# lps_display_rev_g_p1.net
KiCad netlist of a schematic drawn in Altium Designer
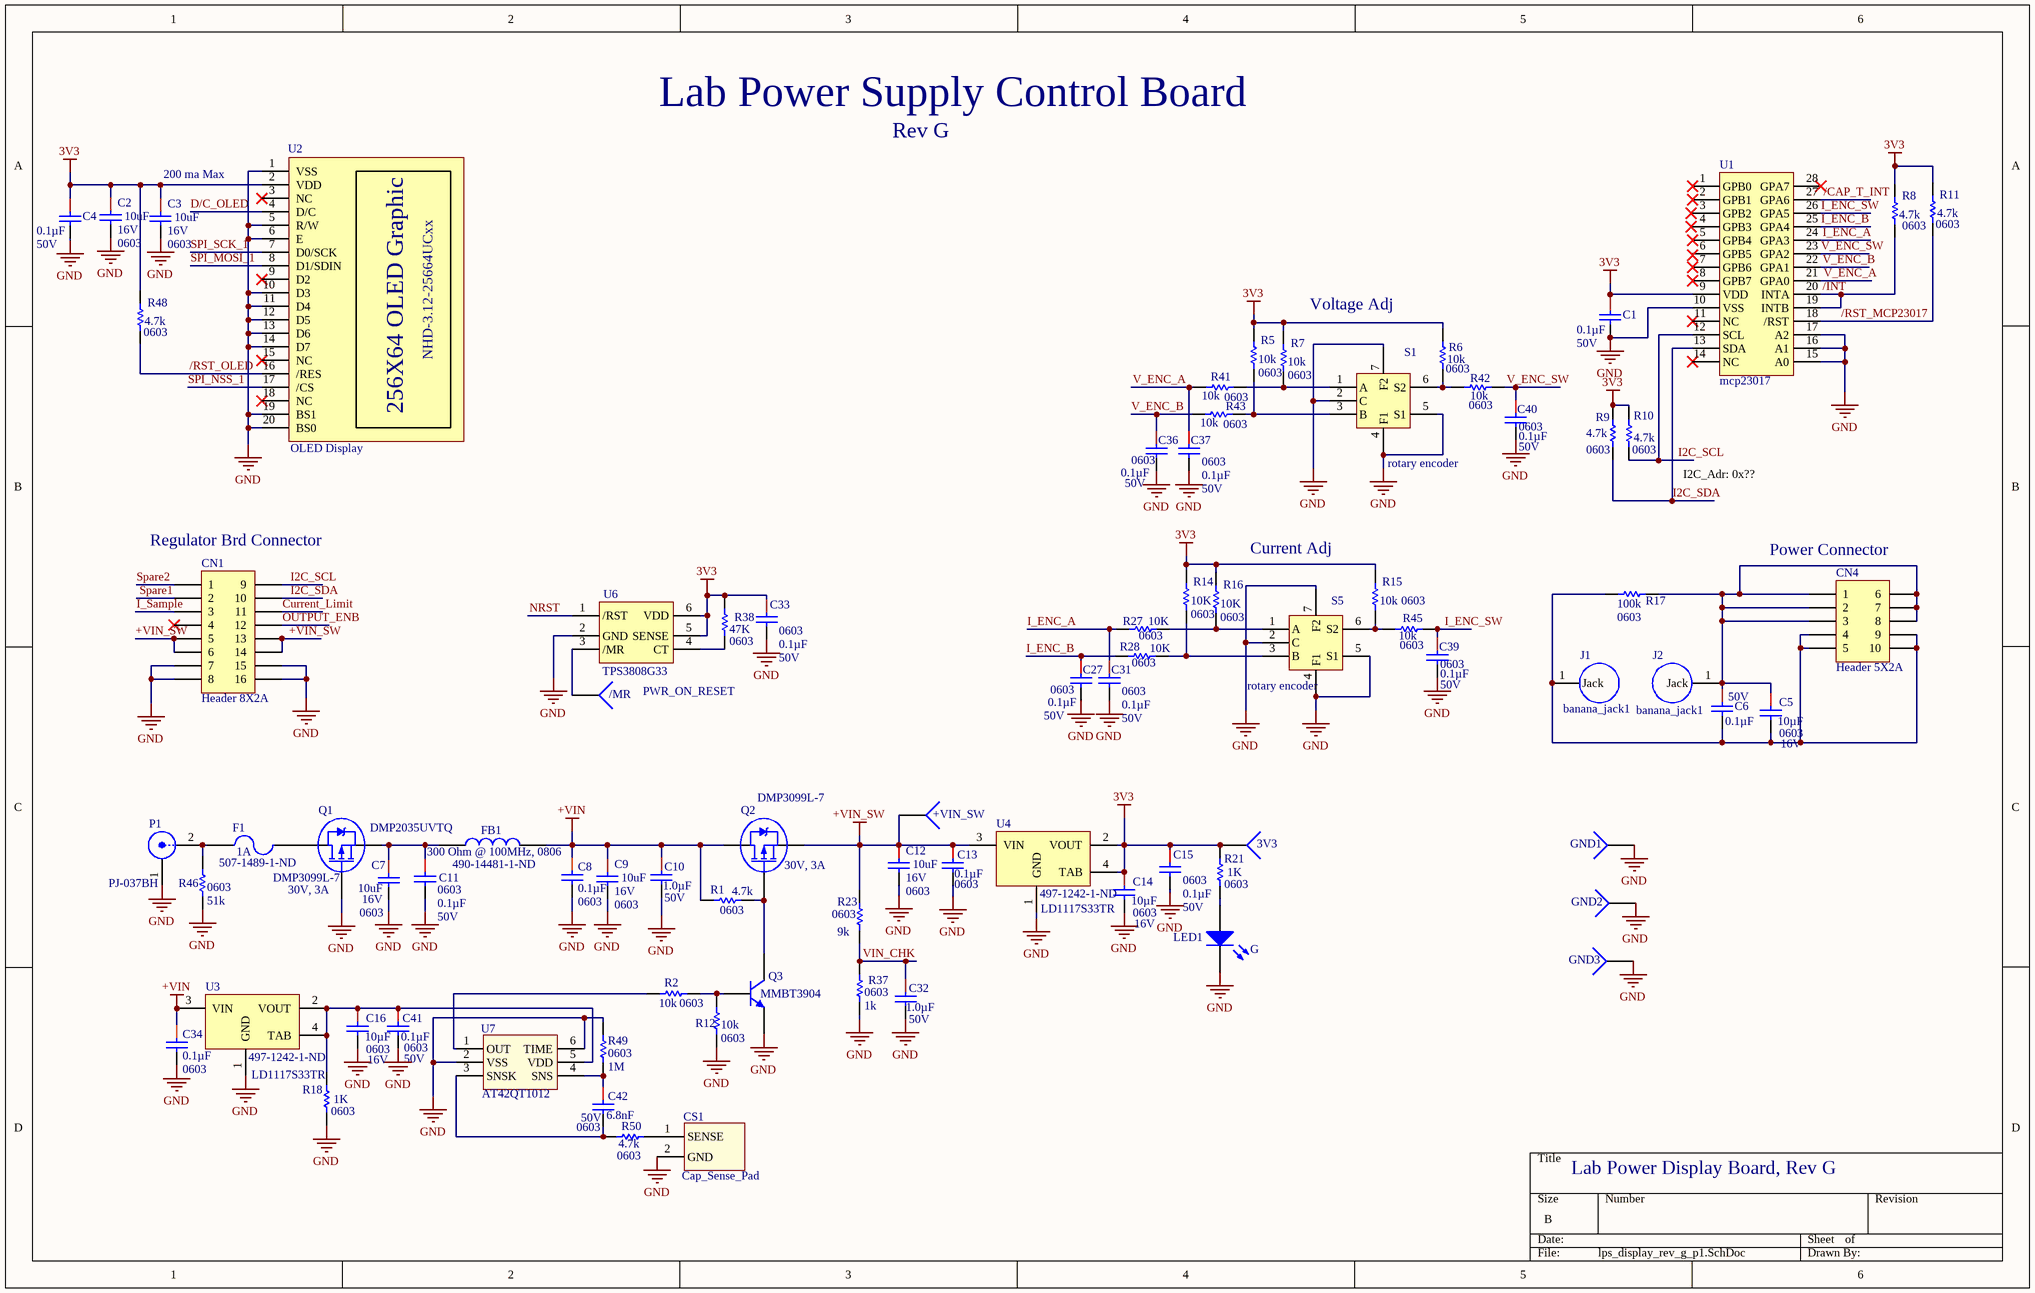
[diagram p0: lps_display_rev_g_p1.SchDoc]

(export (version "E")
  (design (tool "Eeschema 10.0.6"))
  (components
    (comp (ref "+VIN_SW")
      (value "~")
      (footprint "TestPoint-TH 35 mil")
      (description "Test Point")
      (libsource (lib "OLogic-Misc") (part "TestPoint"))
    )
    (comp (ref "/MR")
      (value "~")
      (footprint "TestPoint-TH 35 mil")
      (description "Test Point")
      (libsource (lib "OLogic-Misc") (part "TestPoint"))
    )
    (comp (ref "3V3")
      (value "~")
      (footprint "TestPoint-TH 35 mil")
      (description "Test Point")
      (libsource (lib "OLogic-Misc") (part "TestPoint"))
    )
    (comp (ref "C1")
      (value "0.1uF 0603 50V")
      (footprint "CAPC0603(1608)_N")
      (fields
        (field (name "MANUFACTURER") "Kemet")
        (field (name "MANUFACTURER PART NUMBER") "C0603C104K5RACTU")
        (field (name "TOLERANCE") "±10%")
        (field (name "CAPACITANCE") "0.1µF")
        (field (name "VOLTAGE - RATED") "50V")
      )
      (libsource (lib "OLogic-Passive") (part "CAP CER 0.1UF 50V 10% X7R 0603"))
    )
    (comp (ref "C2")
      (value "10uF")
      (footprint "CAPC0603(1608)_N")
      (description "10UF 0603 16V")
      (fields
        (field (name "MANUFACTURER") "Murata Electronics North America")
        (field (name "MANUFACTURER PART NUMBER") "GRM188R61C106MA73D")
        (field (name "PACKAGE / CASE") "0603")
        (field (name "VOLTAGE - RATED") "16V")
      )
      (libsource (lib "OLogic-Passive") (part "CAP CER 10UF 16V 20% X5R 0603"))
    )
    (comp (ref "C3")
      (value "10uF")
      (footprint "CAPC0603(1608)_N")
      (description "10UF 0603 16V")
      (fields
        (field (name "MANUFACTURER") "Murata Electronics North America")
        (field (name "MANUFACTURER PART NUMBER") "GRM188R61C106MA73D")
        (field (name "PACKAGE / CASE") "0603")
        (field (name "VOLTAGE - RATED") "16V")
      )
      (libsource (lib "OLogic-Passive") (part "CAP CER 10UF 16V 20% X5R 0603"))
    )
    (comp (ref "C4")
      (value "0.1uF 0603 50V")
      (footprint "CAPC0603(1608)_N")
      (fields
        (field (name "MANUFACTURER") "Kemet")
        (field (name "MANUFACTURER PART NUMBER") "C0603C104K5RACTU")
        (field (name "TOLERANCE") "±10%")
        (field (name "CAPACITANCE") "0.1µF")
        (field (name "VOLTAGE - RATED") "50V")
      )
      (libsource (lib "OLogic-Passive") (part "CAP CER 0.1UF 50V 10% X7R 0603"))
    )
    (comp (ref "C5")
      (value "10uF")
      (footprint "CAPC0603(1608)_N")
      (description "10UF 0603 16V")
      (fields
        (field (name "MANUFACTURER") "Murata Electronics North America")
        (field (name "MANUFACTURER PART NUMBER") "GRM188R61C106MA73D")
        (field (name "CAPACITANCE") "10µF")
        (field (name "PACKAGE / CASE") "0603")
        (field (name "VOLTAGE - RATED") "16V")
      )
      (libsource (lib "OLogic-Passive") (part "CAP CER 10UF 16V 20% X5R 0603"))
    )
    (comp (ref "C6")
      (value "0.1uF 0603 50V")
      (footprint "CAPC0603(1608)_N")
      (fields
        (field (name "MANUFACTURER") "Kemet")
        (field (name "MANUFACTURER PART NUMBER") "C0603C104K5RACTU")
        (field (name "TOLERANCE") "±10%")
        (field (name "CAPACITANCE") "0.1µF")
        (field (name "VOLTAGE - RATED") "50V")
      )
      (libsource (lib "OLogic-Passive") (part "CAP CER 0.1UF 50V 10% X7R 0603"))
    )
    (comp (ref "C7")
      (value "10uF")
      (footprint "CAPC0603(1608)_N")
      (description "10UF 0603 16V")
      (fields
        (field (name "MANUFACTURER") "Murata Electronics North America")
        (field (name "MANUFACTURER PART NUMBER") "GRM188R61C106MA73D")
        (field (name "PACKAGE / CASE") "0603")
        (field (name "VOLTAGE - RATED") "16V")
      )
      (libsource (lib "OLogic-Passive") (part "CAP CER 10UF 16V 20% X5R 0603"))
    )
    (comp (ref "C8")
      (value "0.1uF")
      (footprint "CAPC0603(1608)_N")
      (description "0.1uF 0603 16V")
      (fields
        (field (name "MANUFACTURER") "Kemet")
        (field (name "MANUFACTURER PART NUMBER") "C0603C104K4RACTU")
        (field (name "CAPACITANCE") "0.1µF")
        (field (name "PACKAGE / CASE") "0603")
      )
      (libsource (lib "OLogic-Passive") (part "CAP CER 0.1UF 16V 10% X7R 0603"))
    )
    (comp (ref "C9")
      (value "10uF")
      (footprint "CAPC0603(1608)_N")
      (description "10UF 0603 16V")
      (fields
        (field (name "MANUFACTURER") "Murata Electronics North America")
        (field (name "MANUFACTURER PART NUMBER") "GRM188R61C106MA73D")
        (field (name "PACKAGE / CASE") "0603")
        (field (name "VOLTAGE - RATED") "16V")
      )
      (libsource (lib "OLogic-Passive") (part "CAP CER 10UF 16V 20% X5R 0603"))
    )
    (comp (ref "C10")
      (value "0.1uF 0603 50V")
      (footprint "CAPC0603(1608)_N")
      (fields
        (field (name "MANUFACTURER") "Kemet")
        (field (name "MANUFACTURER PART NUMBER") "C0603C104K5RACTU")
        (field (name "TOLERANCE") "±10%")
        (field (name "CAPACITANCE") "1.0µF")
        (field (name "VOLTAGE - RATED") "50V")
      )
      (libsource (lib "OLogic-Passive") (part "CAP CER 0.1UF 50V 10% X7R 0603"))
    )
    (comp (ref "C11")
      (value "0.1uF 0603 50V")
      (footprint "CAPC0603(1608)_N")
      (fields
        (field (name "MANUFACTURER") "Yageo")
        (field (name "MANUFACTURER PART NUMBER") "CC0603ZRY5V9BB104")
        (field (name "TOLERANCE") "-20%, +80%")
        (field (name "PACKAGE / CASE") "0603")
        (field (name "CAPACITANCE") "0.1µF")
        (field (name "VOLTAGE - RATED") "50V")
      )
      (libsource (lib "OLogic-Passive") (part "CAP CER 0.1UF 50V 10% X7R 0603"))
    )
    (comp (ref "C12")
      (value "10uF")
      (footprint "CAPC0603(1608)_N")
      (description "10UF 0603 16V")
      (fields
        (field (name "MANUFACTURER") "Murata Electronics North America")
        (field (name "MANUFACTURER PART NUMBER") "GRM188R61C106MA73D")
        (field (name "PACKAGE / CASE") "0603")
        (field (name "VOLTAGE - RATED") "16V")
      )
      (libsource (lib "OLogic-Passive") (part "CAP CER 10UF 16V 20% X5R 0603"))
    )
    (comp (ref "C13")
      (value "0.47uF")
      (footprint "CAPC0603(1608)_N")
      (description "0.47uF 0603 16V")
      (fields
        (field (name "MANUFACTURER") "Kemet")
        (field (name "MANUFACTURER PART NUMBER") "C0603C474K4RACTU")
        (field (name "PACKAGE / CASE") "0603")
        (field (name "CAPACITANCE") "0.1µF")
      )
      (libsource (lib "OLogic-Passive") (part "CAP CER 0.47UF 16V 10% X7R 0603"))
    )
    (comp (ref "C14")
      (value "10uF")
      (footprint "CAPC0603(1608)_N")
      (description "10UF 0603 16V")
      (fields
        (field (name "MANUFACTURER") "Murata Electronics North America")
        (field (name "MANUFACTURER PART NUMBER") "GRM188R61C106MA73D")
        (field (name "CAPACITANCE") "10µF")
        (field (name "PACKAGE / CASE") "0603")
        (field (name "VOLTAGE - RATED") "16V")
      )
      (libsource (lib "OLogic-Passive") (part "CAP CER 10UF 16V 20% X5R 0603"))
    )
    (comp (ref "C15")
      (value "0.1uF 0603 50V")
      (footprint "CAPC0603(1608)_N")
      (fields
        (field (name "MANUFACTURER") "Yageo")
        (field (name "MANUFACTURER PART NUMBER") "CC0603ZRY5V9BB104")
        (field (name "TOLERANCE") "-20%, +80%")
        (field (name "PACKAGE / CASE") "0603")
        (field (name "CAPACITANCE") "0.1µF")
        (field (name "VOLTAGE - RATED") "50V")
      )
      (libsource (lib "OLogic-Passive") (part "CAP CER 0.1UF 50V 10% X7R 0603"))
    )
    (comp (ref "C16")
      (value "10uF")
      (footprint "CAPC0603(1608)_N")
      (description "10UF 0603 16V")
      (fields
        (field (name "MANUFACTURER") "Murata Electronics North America")
        (field (name "MANUFACTURER PART NUMBER") "GRM188R61C106MA73D")
        (field (name "CAPACITANCE") "10µF")
        (field (name "PACKAGE / CASE") "0603")
        (field (name "VOLTAGE - RATED") "16V")
      )
      (libsource (lib "OLogic-Passive") (part "CAP CER 10UF 16V 20% X5R 0603"))
    )
    (comp (ref "C27")
      (value "0.1uF 0603 50V")
      (footprint "CAPC0603(1608)_N")
      (fields
        (field (name "MANUFACTURER") "Yageo")
        (field (name "MANUFACTURER PART NUMBER") "CC0603ZRY5V9BB104")
        (field (name "TOLERANCE") "-20%, +80%")
        (field (name "PACKAGE / CASE") "0603")
        (field (name "CAPACITANCE") "0.1µF")
        (field (name "VOLTAGE - RATED") "50V")
      )
      (libsource (lib "OLogic-Passive") (part "CAP CER 0.1UF 50V 10% X7R 0603"))
    )
    (comp (ref "C31")
      (value "0.1uF 0603 50V")
      (footprint "CAPC0603(1608)_N")
      (fields
        (field (name "MANUFACTURER") "Yageo")
        (field (name "MANUFACTURER PART NUMBER") "CC0603ZRY5V9BB104")
        (field (name "TOLERANCE") "-20%, +80%")
        (field (name "PACKAGE / CASE") "0603")
        (field (name "CAPACITANCE") "0.1µF")
        (field (name "VOLTAGE - RATED") "50V")
      )
      (libsource (lib "OLogic-Passive") (part "CAP CER 0.1UF 50V 10% X7R 0603"))
    )
    (comp (ref "C32")
      (value "0.1uF 0603 50V")
      (footprint "CAPC0603(1608)_N")
      (fields
        (field (name "MANUFACTURER") "Kemet")
        (field (name "MANUFACTURER PART NUMBER") "C0603C104K5RACTU")
        (field (name "TOLERANCE") "±10%")
        (field (name "CAPACITANCE") "1.0µF")
        (field (name "VOLTAGE - RATED") "50V")
      )
      (libsource (lib "OLogic-Passive") (part "CAP CER 0.1UF 50V 10% X7R 0603"))
    )
    (comp (ref "C33")
      (value "0.1uF 0603 50V")
      (footprint "CAPC0603(1608)_N")
      (fields
        (field (name "MANUFACTURER") "Yageo")
        (field (name "MANUFACTURER PART NUMBER") "CC0603ZRY5V9BB104")
        (field (name "TOLERANCE") "-20%, +80%")
        (field (name "PACKAGE / CASE") "0603")
        (field (name "CAPACITANCE") "0.1µF")
        (field (name "VOLTAGE - RATED") "50V")
      )
      (libsource (lib "OLogic-Passive") (part "CAP CER 0.1UF 50V 10% X7R 0603"))
    )
    (comp (ref "C34")
      (value "0.1uF")
      (footprint "CAPC0603(1608)_N")
      (description "0.1uF 0603 16V")
      (fields
        (field (name "MANUFACTURER") "Kemet")
        (field (name "MANUFACTURER PART NUMBER") "C0603C104K4RACTU")
        (field (name "CAPACITANCE") "0.1µF")
        (field (name "PACKAGE / CASE") "0603")
      )
      (libsource (lib "OLogic-Passive") (part "CAP CER 0.1UF 16V 10% X7R 0603"))
    )
    (comp (ref "C36")
      (value "0.1uF 0603 50V")
      (footprint "CAPC0603(1608)_N")
      (fields
        (field (name "MANUFACTURER") "Yageo")
        (field (name "MANUFACTURER PART NUMBER") "CC0603ZRY5V9BB104")
        (field (name "TOLERANCE") "-20%, +80%")
        (field (name "PACKAGE / CASE") "0603")
        (field (name "CAPACITANCE") "0.1µF")
        (field (name "VOLTAGE - RATED") "50V")
      )
      (libsource (lib "OLogic-Passive") (part "CAP CER 0.1UF 50V 10% X7R 0603"))
    )
    (comp (ref "C37")
      (value "0.1uF 0603 50V")
      (footprint "CAPC0603(1608)_N")
      (fields
        (field (name "MANUFACTURER") "Yageo")
        (field (name "MANUFACTURER PART NUMBER") "CC0603ZRY5V9BB104")
        (field (name "TOLERANCE") "-20%, +80%")
        (field (name "PACKAGE / CASE") "0603")
        (field (name "CAPACITANCE") "0.1µF")
        (field (name "VOLTAGE - RATED") "50V")
      )
      (libsource (lib "OLogic-Passive") (part "CAP CER 0.1UF 50V 10% X7R 0603"))
    )
    (comp (ref "C39")
      (value "0.1uF 0603 50V")
      (footprint "CAPC0603(1608)_N")
      (fields
        (field (name "MANUFACTURER") "Yageo")
        (field (name "MANUFACTURER PART NUMBER") "CC0603ZRY5V9BB104")
        (field (name "TOLERANCE") "-20%, +80%")
        (field (name "PACKAGE / CASE") "0603")
        (field (name "CAPACITANCE") "0.1µF")
        (field (name "VOLTAGE - RATED") "50V")
      )
      (libsource (lib "OLogic-Passive") (part "CAP CER 0.1UF 50V 10% X7R 0603"))
    )
    (comp (ref "C40")
      (value "0.1uF 0603 50V")
      (footprint "CAPC0603(1608)_N")
      (fields
        (field (name "MANUFACTURER") "Yageo")
        (field (name "MANUFACTURER PART NUMBER") "CC0603ZRY5V9BB104")
        (field (name "TOLERANCE") "-20%, +80%")
        (field (name "PACKAGE / CASE") "0603")
        (field (name "CAPACITANCE") "0.1µF")
        (field (name "VOLTAGE - RATED") "50V")
      )
      (libsource (lib "OLogic-Passive") (part "CAP CER 0.1UF 50V 10% X7R 0603"))
    )
    (comp (ref "C41")
      (value "0.1uF 0603 50V")
      (footprint "CAPC0603(1608)_N")
      (fields
        (field (name "MANUFACTURER") "Yageo")
        (field (name "MANUFACTURER PART NUMBER") "CC0603ZRY5V9BB104")
        (field (name "TOLERANCE") "-20%, +80%")
        (field (name "PACKAGE / CASE") "0603")
        (field (name "CAPACITANCE") "0.1µF")
        (field (name "VOLTAGE - RATED") "50V")
      )
      (libsource (lib "OLogic-Passive") (part "CAP CER 0.1UF 50V 10% X7R 0603"))
    )
    (comp (ref "C42")
      (value "0.1uF 0603 50V")
      (footprint "CAPC0603(1608)_N")
      (fields
        (field (name "MANUFACTURER") "Yageo")
        (field (name "MANUFACTURER PART NUMBER") "CC0603ZRY5V9BB104")
        (field (name "TOLERANCE") "-20%, +80%")
        (field (name "PACKAGE / CASE") "0603")
        (field (name "CAPACITANCE") "6.8nF")
        (field (name "VOLTAGE - RATED") "50V")
      )
      (libsource (lib "OLogic-Passive") (part "CAP CER 0.1UF 50V 10% X7R 0603"))
    )
    (comp (ref "CN1")
      (value "Header 8X2A")
      (footprint "HDR2X8_CEN")
      (description "Header, 8-Pin, Dual row")
      (fields (field (name "PUBLISHER") "Altium Limited"))
      (libsource (lib "OLogic Nexus Vault") (part "Header 8X2A"))
    )
    (comp (ref "CN4")
      (value "Header 5X2A")
      (footprint "HDR2X5_CEN")
      (description "Header, 5-Pin, Dual row")
      (fields (field (name "PUBLISHER") "Altium Limited"))
      (libsource (lib "OLogic Nexus Vault") (part "Header 5X2A"))
    )
    (comp (ref "CS1")
      (value "Cap_Sense_Pad")
      (footprint "CAP_TOUCH_ROUND")
      (libsource (lib "*") (part "Cap_Sense_Pad"))
    )
    (comp (ref "F1")
      (value "1A")
      (footprint "PTC-3225[1210]")
      (description "1A PTC Fuse")
      (fields (field (name "MANUFACTURER") "Bel Fuse") (field (name "MPN") "0ZCB0050FF2G"))
      (libsource (lib "OLogic-Misc") (part "0ZCB0050FF2G"))
    )
    (comp (ref "FB1")
      (value "300 Ohm @ 100MHz, 0806")
      (footprint "RESC0805(2012)_M")
      (description "40 OHM 0805 1.5A")
      (fields
        (field (name "MANUFACTURER") "Laird-Signal Integrity Products")
        (field (name "MANUFACTURER PART NUMBER") "MI0805K400R-10")
        (field (name "CREATOR") "osman")
      )
      (libsource (lib "OLogic-Passive") (part "FERRITE 40 OHM 1.5A 0805"))
    )
    (comp (ref "GND1")
      (value "~")
      (footprint "TestPoint-TH 35 mil")
      (description "Test Point")
      (libsource (lib "OLogic-Misc") (part "TestPoint"))
    )
    (comp (ref "GND2")
      (value "~")
      (footprint "TestPoint-TH 35 mil")
      (description "Test Point")
      (libsource (lib "OLogic-Misc") (part "TestPoint"))
    )
    (comp (ref "GND3")
      (value "~")
      (footprint "TestPoint-TH 35 mil")
      (description "Test Point")
      (libsource (lib "OLogic-Misc") (part "TestPoint"))
    )
    (comp (ref "J1")
      (value "banana_jack1")
      (footprint "Banana_jack1")
      (libsource (lib "lab power supply") (part "banana_jack1"))
    )
    (comp (ref "J2")
      (value "banana_jack1")
      (footprint "Banana_jack1")
      (libsource (lib "lab power supply") (part "banana_jack1"))
    )
    (comp (ref "LED1")
      (value "G")
      (footprint "SM-LED-0603")
      (description "0603 SMD LED")
      (libsource (lib "OLogic-Diode-Opto-LED") (part "0603 LED"))
    )
    (comp (ref "P1")
      (value "PJ-037BH")
      (footprint "pwrplug")
      (description "2.5x5.5mm Power Jack")
      (fields (field (name "MANUFACTURER") "CUI Inc"))
      (libsource (lib "OLogic-Connectors") (part "PJ-037BH"))
    )
    (comp (ref "Q1")
      (value "DMP3099L-7")
      (footprint "SOT23")
      (description "MOSFET P-CH 30V SOT23")
      (fields (field (name "MANUFACTURER") "Diodes Incorporated") (field (name "TEXT") "30V, 3A"))
      (libsource (lib "OLogic-Trans-Drivers") (part "DMP3099L-7"))
    )
    (comp (ref "Q2")
      (value "DMP3099L-7")
      (footprint "SOT23")
      (description "MOSFET P-CH 30V SOT23")
      (fields (field (name "MANUFACTURER") "Diodes Incorporated") (field (name "TEXT") "30V, 3A"))
      (libsource (lib "OLogic-Trans-Drivers") (part "DMP3099L-7"))
    )
    (comp (ref "Q3")
      (value "MMBT3904")
      (footprint "SOT23")
      (description "NPN General Purpose Amplifier")
      (fields (field (name "MANUFACTURER") "ON Semiconductor") (field (name "MPN") "MMBT3904WT1G"))
      (libsource (lib "OLogic-Trans-Drivers") (part "MMBT3904"))
    )
    (comp (ref "R1")
      (value "4.7K")
      (footprint "RESC0603(1608)_N")
      (description "4.7K 0603")
      (fields
        (field (name "MANUFACTURER") "Panasonic Electronic Components")
        (field (name "MANUFACTURER PART NUMBER") "ERJ-3GEYJ472V")
        (field (name "RESISTANCE (OHMS)") "4.7k")
        (field (name "PACKAGE / CASE") "0603")
      )
      (libsource (lib "OLogic-Passive") (part "RES 4.7K OHM 1/10W 5% 0603 SMD"))
    )
    (comp (ref "R2")
      (value "4.7K")
      (footprint "RESC0603(1608)_N")
      (description "4.7K 0603")
      (fields
        (field (name "MANUFACTURER") "Panasonic Electronic Components")
        (field (name "MANUFACTURER PART NUMBER") "ERJ-3GEYJ472V")
        (field (name "RESISTANCE (OHMS)") "10k")
        (field (name "PACKAGE / CASE") "0603")
      )
      (libsource (lib "OLogic-Passive") (part "RES 4.7K OHM 1/10W 5% 0603 SMD"))
    )
    (comp (ref "R5")
      (value "4.7K")
      (footprint "RESC0603(1608)_N")
      (description "4.7K 0603")
      (fields
        (field (name "MANUFACTURER") "Panasonic Electronic Components")
        (field (name "MANUFACTURER PART NUMBER") "ERJ-3GEYJ472V")
        (field (name "RESISTANCE (OHMS)") "10k")
        (field (name "PACKAGE / CASE") "0603")
      )
      (libsource (lib "OLogic-Passive") (part "RES 4.7K OHM 1/10W 5% 0603 SMD"))
    )
    (comp (ref "R6")
      (value "4.7K")
      (footprint "RESC0603(1608)_N")
      (description "4.7K 0603")
      (fields
        (field (name "MANUFACTURER") "Panasonic Electronic Components")
        (field (name "MANUFACTURER PART NUMBER") "ERJ-3GEYJ472V")
        (field (name "RESISTANCE (OHMS)") "10k")
        (field (name "PACKAGE / CASE") "0603")
      )
      (libsource (lib "OLogic-Passive") (part "RES 4.7K OHM 1/10W 5% 0603 SMD"))
    )
    (comp (ref "R7")
      (value "4.7K")
      (footprint "RESC0603(1608)_N")
      (description "4.7K 0603")
      (fields
        (field (name "MANUFACTURER") "Panasonic Electronic Components")
        (field (name "MANUFACTURER PART NUMBER") "ERJ-3GEYJ472V")
        (field (name "RESISTANCE (OHMS)") "10k")
        (field (name "PACKAGE / CASE") "0603")
      )
      (libsource (lib "OLogic-Passive") (part "RES 4.7K OHM 1/10W 5% 0603 SMD"))
    )
    (comp (ref "R8")
      (value "4.7K")
      (footprint "RESC0603(1608)_N")
      (description "4.7K 0603")
      (fields
        (field (name "MANUFACTURER") "Panasonic Electronic Components")
        (field (name "MANUFACTURER PART NUMBER") "ERJ-3GEYJ472V")
        (field (name "RESISTANCE (OHMS)") "4.7k")
        (field (name "PACKAGE / CASE") "0603")
      )
      (libsource (lib "OLogic-Passive") (part "RES 4.7K OHM 1/10W 5% 0603 SMD"))
    )
    (comp (ref "R9")
      (value "4.7K")
      (footprint "RESC0603(1608)_N")
      (description "4.7K 0603")
      (fields
        (field (name "MANUFACTURER") "Panasonic Electronic Components")
        (field (name "MANUFACTURER PART NUMBER") "ERJ-3GEYJ472V")
        (field (name "RESISTANCE (OHMS)") "4.7k")
        (field (name "PACKAGE / CASE") "0603")
      )
      (libsource (lib "OLogic-Passive") (part "RES 4.7K OHM 1/10W 5% 0603 SMD"))
    )
    (comp (ref "R10")
      (value "4.7K")
      (footprint "RESC0603(1608)_N")
      (description "4.7K 0603")
      (fields
        (field (name "MANUFACTURER") "Panasonic Electronic Components")
        (field (name "MANUFACTURER PART NUMBER") "ERJ-3GEYJ472V")
        (field (name "RESISTANCE (OHMS)") "4.7k")
        (field (name "PACKAGE / CASE") "0603")
      )
      (libsource (lib "OLogic-Passive") (part "RES 4.7K OHM 1/10W 5% 0603 SMD"))
    )
    (comp (ref "R11")
      (value "4.7K")
      (footprint "RESC0603(1608)_N")
      (description "4.7K 0603")
      (fields
        (field (name "MANUFACTURER") "Panasonic Electronic Components")
        (field (name "MANUFACTURER PART NUMBER") "ERJ-3GEYJ472V")
        (field (name "RESISTANCE (OHMS)") "4.7k")
        (field (name "PACKAGE / CASE") "0603")
      )
      (libsource (lib "OLogic-Passive") (part "RES 4.7K OHM 1/10W 5% 0603 SMD"))
    )
    (comp (ref "R12")
      (value "4.7K")
      (footprint "RESC0603(1608)_N")
      (description "4.7K 0603")
      (fields
        (field (name "MANUFACTURER") "Panasonic Electronic Components")
        (field (name "MANUFACTURER PART NUMBER") "ERJ-3GEYJ472V")
        (field (name "RESISTANCE (OHMS)") "10k")
        (field (name "PACKAGE / CASE") "0603")
      )
      (libsource (lib "OLogic-Passive") (part "RES 4.7K OHM 1/10W 5% 0603 SMD"))
    )
    (comp (ref "R14")
      (value "4.7K")
      (footprint "RESC0603(1608)_N")
      (description "4.7K 0603")
      (fields
        (field (name "MANUFACTURER") "Panasonic Electronic Components")
        (field (name "MANUFACTURER PART NUMBER") "ERJ-3GEYJ472V")
        (field (name "RESISTANCE (OHMS)") "10K")
        (field (name "PACKAGE / CASE") "0603")
      )
      (libsource (lib "OLogic-Passive") (part "RES 4.7K OHM 1/10W 5% 0603 SMD"))
    )
    (comp (ref "R15")
      (value "4.7K")
      (footprint "RESC0603(1608)_N")
      (description "4.7K 0603")
      (fields
        (field (name "MANUFACTURER") "Panasonic Electronic Components")
        (field (name "MANUFACTURER PART NUMBER") "ERJ-3GEYJ472V")
        (field (name "RESISTANCE (OHMS)") "10k")
        (field (name "PACKAGE / CASE") "0603")
      )
      (libsource (lib "OLogic-Passive") (part "RES 4.7K OHM 1/10W 5% 0603 SMD"))
    )
    (comp (ref "R16")
      (value "4.7K")
      (footprint "RESC0603(1608)_N")
      (description "4.7K 0603")
      (fields
        (field (name "MANUFACTURER") "Panasonic Electronic Components")
        (field (name "MANUFACTURER PART NUMBER") "ERJ-3GEYJ472V")
        (field (name "RESISTANCE (OHMS)") "10K")
        (field (name "PACKAGE / CASE") "0603")
      )
      (libsource (lib "OLogic-Passive") (part "RES 4.7K OHM 1/10W 5% 0603 SMD"))
    )
    (comp (ref "R17")
      (value "4.7K")
      (footprint "RESC0603(1608)_N")
      (description "4.7K 0603")
      (fields
        (field (name "MANUFACTURER") "Panasonic Electronic Components")
        (field (name "MANUFACTURER PART NUMBER") "ERJ-3GEYJ472V")
        (field (name "RESISTANCE (OHMS)") "100k")
        (field (name "PACKAGE / CASE") "0603")
      )
      (libsource (lib "OLogic-Passive") (part "RES 4.7K OHM 1/10W 5% 0603 SMD"))
    )
    (comp (ref "R18")
      (value "4.7K")
      (footprint "RESC0603(1608)_N")
      (description "4.7K 0603")
      (fields
        (field (name "MANUFACTURER") "Panasonic Electronic Components")
        (field (name "MANUFACTURER PART NUMBER") "ERJ-3GEYJ472V")
        (field (name "RESISTANCE (OHMS)") "1K")
        (field (name "PACKAGE / CASE") "0603")
      )
      (libsource (lib "OLogic-Passive") (part "RES 4.7K OHM 1/10W 5% 0603 SMD"))
    )
    (comp (ref "R21")
      (value "4.7K")
      (footprint "RESC0603(1608)_N")
      (description "4.7K 0603")
      (fields
        (field (name "MANUFACTURER") "Panasonic Electronic Components")
        (field (name "MANUFACTURER PART NUMBER") "ERJ-3GEYJ472V")
        (field (name "RESISTANCE (OHMS)") "1K")
        (field (name "PACKAGE / CASE") "0603")
      )
      (libsource (lib "OLogic-Passive") (part "RES 4.7K OHM 1/10W 5% 0603 SMD"))
    )
    (comp (ref "R23")
      (value "1.0K")
      (footprint "RESC0603(1608)_N")
      (description "1.0K 0603")
      (fields
        (field (name "MANUFACTURER") "Stackpole Electronics Inc.")
        (field (name "MANUFACTURER PART NUMBER") "RMCF0603FT1K00")
        (field (name "PACKAGE / CASE") "0603")
        (field (name "RESISTANCE (OHMS)") "9k")
      )
      (libsource (lib "OLogic-Passive") (part "RES 1K OHM 1% 1/10W 0603"))
    )
    (comp (ref "R27")
      (value "4.7K")
      (footprint "RESC0603(1608)_N")
      (description "4.7K 0603")
      (fields
        (field (name "MANUFACTURER") "Panasonic Electronic Components")
        (field (name "MANUFACTURER PART NUMBER") "ERJ-3GEYJ472V")
        (field (name "RESISTANCE (OHMS)") "10K")
        (field (name "PACKAGE / CASE") "0603")
      )
      (libsource (lib "OLogic-Passive") (part "RES 4.7K OHM 1/10W 5% 0603 SMD"))
    )
    (comp (ref "R28")
      (value "4.7K")
      (footprint "RESC0603(1608)_N")
      (description "4.7K 0603")
      (fields
        (field (name "MANUFACTURER") "Panasonic Electronic Components")
        (field (name "MANUFACTURER PART NUMBER") "ERJ-3GEYJ472V")
        (field (name "RESISTANCE (OHMS)") "10K")
        (field (name "PACKAGE / CASE") "0603")
      )
      (libsource (lib "OLogic-Passive") (part "RES 4.7K OHM 1/10W 5% 0603 SMD"))
    )
    (comp (ref "R37")
      (value "1.0K")
      (footprint "RESC0603(1608)_N")
      (description "1.0K 0603")
      (fields
        (field (name "MANUFACTURER") "Stackpole Electronics Inc.")
        (field (name "MANUFACTURER PART NUMBER") "RMCF0603FT1K00")
        (field (name "PACKAGE / CASE") "0603")
        (field (name "RESISTANCE (OHMS)") "1k")
      )
      (libsource (lib "OLogic-Passive") (part "RES 1K OHM 1% 1/10W 0603"))
    )
    (comp (ref "R38")
      (value "4.7K")
      (footprint "RESC0603(1608)_N")
      (description "4.7K 0603")
      (fields
        (field (name "MANUFACTURER") "Panasonic Electronic Components")
        (field (name "MANUFACTURER PART NUMBER") "ERJ-3GEYJ472V")
        (field (name "RESISTANCE (OHMS)") "47K")
        (field (name "PACKAGE / CASE") "0603")
      )
      (libsource (lib "OLogic-Passive") (part "RES 4.7K OHM 1/10W 5% 0603 SMD"))
    )
    (comp (ref "R41")
      (value "4.7K")
      (footprint "RESC0603(1608)_N")
      (description "4.7K 0603")
      (fields
        (field (name "MANUFACTURER") "Panasonic Electronic Components")
        (field (name "MANUFACTURER PART NUMBER") "ERJ-3GEYJ472V")
        (field (name "RESISTANCE (OHMS)") "10k")
        (field (name "PACKAGE / CASE") "0603")
      )
      (libsource (lib "OLogic-Passive") (part "RES 4.7K OHM 1/10W 5% 0603 SMD"))
    )
    (comp (ref "R42")
      (value "4.7K")
      (footprint "RESC0603(1608)_N")
      (description "4.7K 0603")
      (fields
        (field (name "MANUFACTURER") "Panasonic Electronic Components")
        (field (name "MANUFACTURER PART NUMBER") "ERJ-3GEYJ472V")
        (field (name "RESISTANCE (OHMS)") "10k")
        (field (name "PACKAGE / CASE") "0603")
      )
      (libsource (lib "OLogic-Passive") (part "RES 4.7K OHM 1/10W 5% 0603 SMD"))
    )
    (comp (ref "R43")
      (value "4.7K")
      (footprint "RESC0603(1608)_N")
      (description "4.7K 0603")
      (fields
        (field (name "MANUFACTURER") "Panasonic Electronic Components")
        (field (name "MANUFACTURER PART NUMBER") "ERJ-3GEYJ472V")
        (field (name "RESISTANCE (OHMS)") "10k")
        (field (name "PACKAGE / CASE") "0603")
      )
      (libsource (lib "OLogic-Passive") (part "RES 4.7K OHM 1/10W 5% 0603 SMD"))
    )
    (comp (ref "R45")
      (value "4.7K")
      (footprint "RESC0603(1608)_N")
      (description "4.7K 0603")
      (fields
        (field (name "MANUFACTURER") "Panasonic Electronic Components")
        (field (name "MANUFACTURER PART NUMBER") "ERJ-3GEYJ472V")
        (field (name "RESISTANCE (OHMS)") "10k")
        (field (name "PACKAGE / CASE") "0603")
      )
      (libsource (lib "OLogic-Passive") (part "RES 4.7K OHM 1/10W 5% 0603 SMD"))
    )
    (comp (ref "R46")
      (value "1.0K")
      (footprint "RESC0603(1608)_N")
      (description "1.0K 0603")
      (fields
        (field (name "MANUFACTURER") "Stackpole Electronics Inc.")
        (field (name "MANUFACTURER PART NUMBER") "RMCF0603FT1K00")
        (field (name "PACKAGE / CASE") "0603")
        (field (name "RESISTANCE (OHMS)") "51k")
      )
      (libsource (lib "OLogic-Passive") (part "RES 1K OHM 1% 1/10W 0603"))
    )
    (comp (ref "R48")
      (value "4.7K")
      (footprint "RESC0603(1608)_N")
      (description "4.7K 0603")
      (fields
        (field (name "MANUFACTURER") "Panasonic Electronic Components")
        (field (name "MANUFACTURER PART NUMBER") "ERJ-3GEYJ472V")
        (field (name "RESISTANCE (OHMS)") "4.7k")
        (field (name "PACKAGE / CASE") "0603")
      )
      (libsource (lib "OLogic-Passive") (part "RES 4.7K OHM 1/10W 5% 0603 SMD"))
    )
    (comp (ref "R49")
      (value "1.0K")
      (footprint "RESC0603(1608)_N")
      (description "1.0K 0603")
      (fields
        (field (name "MANUFACTURER") "Stackpole Electronics Inc.")
        (field (name "MANUFACTURER PART NUMBER") "RMCF0603FT1K00")
        (field (name "PACKAGE / CASE") "0603")
        (field (name "RESISTANCE (OHMS)") "1M")
      )
      (libsource (lib "OLogic-Passive") (part "RES 1K OHM 1% 1/10W 0603"))
    )
    (comp (ref "R50")
      (value "1.0K")
      (footprint "RESC0603(1608)_N")
      (description "1.0K 0603")
      (fields
        (field (name "MANUFACTURER") "Stackpole Electronics Inc.")
        (field (name "MANUFACTURER PART NUMBER") "RMCF0603FT1K00")
        (field (name "PACKAGE / CASE") "0603")
        (field (name "RESISTANCE (OHMS)") "4.7k")
      )
      (libsource (lib "OLogic-Passive") (part "RES 1K OHM 1% 1/10W 0603"))
    )
    (comp (ref "S1")
      (value "rotary encoder")
      (footprint "rotary encoder")
      (libsource (lib "hdmi_lvds") (part "rotary encoder"))
    )
    (comp (ref "S5")
      (value "rotary encoder")
      (footprint "rotary encoder")
      (libsource (lib "hdmi_lvds") (part "rotary encoder"))
    )
    (comp (ref "U1")
      (value "mcp23017")
      (footprint "SOIC28")
      (description "I2C 16 bit Expander")
      (libsource (lib "hdmi_lvds") (part "mcp23017"))
    )
    (comp (ref "U2")
      (value "OLED Display")
      (footprint "oled_graphic_256X64")
      (libsource (lib "*") (part "OLED_Graphic_240x64"))
    )
    (comp (ref "U3")
      (value "3.3V")
      (footprint "DSO-G3")
      (description "3.3 volt fixed regulator, 800mA")
      (fields (field (name "SUPPLIER PART NUMBER 1") "497-1242-1-ND"))
      (libsource (lib "OLogic-Reg-Convert") (part "LD1117S33"))
    )
    (comp (ref "U4")
      (value "3.3V")
      (footprint "DSO-G3")
      (description "3.3 volt fixed regulator, 800mA")
      (fields (field (name "SUPPLIER PART NUMBER 1") "497-1242-1-ND"))
      (libsource (lib "OLogic-Reg-Convert") (part "LD1117S33"))
    )
    (comp (ref "U6") (value "TPS3808G33") (footprint "SOt-23-6") (libsource (lib "*") (part "TPS3808G33")))
    (comp (ref "U7")
      (value "AT42QT1012")
      (footprint "SOt-23-6")
      (description "CAP QTouch Chip")
      (libsource (lib "*") (part "AT42QT1012"))
    )
  )
  (nets
    (net (code "1") (name "+VIN") (class "Default")
      (node (ref "C10") (pin "1") (pinfunction "1_1") (pintype "passive"))
      (node (ref "C34") (pin "1") (pinfunction "1_1") (pintype "passive"))
      (node (ref "C8") (pin "1") (pinfunction "1_1") (pintype "passive"))
      (node (ref "C9") (pin "1") (pinfunction "1_1") (pintype "passive"))
      (node (ref "FB1") (pin "2") (pinfunction "2_2") (pintype "passive"))
      (node (ref "Q2") (pin "3") (pinfunction "D_3") (pintype "passive"))
      (node (ref "R1") (pin "2") (pinfunction "2_2") (pintype "passive"))
      (node (ref "U3") (pin "3") (pinfunction "VIN_3") (pintype "power_in"))
    )
    (net (code "2") (name "+VIN_SW") (class "Default")
      (node (ref "+VIN_SW") (pin "1") (pinfunction "1_1") (pintype "passive"))
      (node (ref "C12") (pin "1") (pinfunction "1_1") (pintype "passive"))
      (node (ref "C13") (pin "1") (pinfunction "1_1") (pintype "passive"))
      (node (ref "CN1") (pin "13") (pinfunction "13_13") (pintype "passive"))
      (node (ref "CN1") (pin "14") (pinfunction "14_14") (pintype "passive"))
      (node (ref "CN1") (pin "5") (pinfunction "5_5") (pintype "passive"))
      (node (ref "CN1") (pin "6") (pinfunction "6_6") (pintype "passive"))
      (node (ref "Q2") (pin "2") (pinfunction "S_2") (pintype "passive"))
      (node (ref "R23") (pin "2") (pinfunction "2_2") (pintype "passive"))
      (node (ref "U4") (pin "3") (pinfunction "VIN_3") (pintype "power_in"))
    )
    (net (code "3") (name "/Current_Limit") (class "Default")
      (node (ref "CN1") (pin "11") (pinfunction "11_11") (pintype "passive"))
    )
    (net (code "4") (name "/D{slash}C_OLED") (class "Default")
      (node (ref "U2") (pin "4") (pinfunction "D/C_4") (pintype "passive"))
    )
    (net (code "5") (name "/I2C_SCL") (class "Default")
      (node (ref "CN1") (pin "9") (pinfunction "9_9") (pintype "passive"))
      (node (ref "R10") (pin "1") (pinfunction "1_1") (pintype "passive"))
      (node (ref "U1") (pin "12") (pinfunction "SCL_12") (pintype "passive"))
    )
    (net (code "6") (name "/I2C_SDA") (class "Default")
      (node (ref "CN1") (pin "10") (pinfunction "10_10") (pintype "passive"))
      (node (ref "R9") (pin "1") (pinfunction "1_1") (pintype "passive"))
      (node (ref "U1") (pin "13") (pinfunction "SDA_13") (pintype "passive"))
    )
    (net (code "7") (name "/I_ENC_A") (class "Default")
      (node (ref "C31") (pin "1") (pinfunction "1_1") (pintype "passive"))
      (node (ref "R27") (pin "2") (pinfunction "2_2") (pintype "passive"))
      (node (ref "U1") (pin "24") (pinfunction "GPA3_24") (pintype "passive"))
    )
    (net (code "8") (name "/I_ENC_B") (class "Default")
      (node (ref "C27") (pin "1") (pinfunction "1_1") (pintype "passive"))
      (node (ref "R28") (pin "2") (pinfunction "2_2") (pintype "passive"))
      (node (ref "U1") (pin "25") (pinfunction "GPA4_25") (pintype "passive"))
    )
    (net (code "9") (name "/I_ENC_SW") (class "Default")
      (node (ref "C39") (pin "1") (pinfunction "1_1") (pintype "passive"))
      (node (ref "R45") (pin "1") (pinfunction "1_1") (pintype "passive"))
      (node (ref "U1") (pin "26") (pinfunction "GPA5_26") (pintype "passive"))
    )
    (net (code "10") (name "/I_Sample") (class "Default")
      (node (ref "CN1") (pin "3") (pinfunction "3_3") (pintype "passive"))
    )
    (net (code "11") (name "/NRST") (class "Default")
      (node (ref "U6") (pin "1") (pinfunction "/RST_1") (pintype "passive"))
    )
    (net (code "12") (name "/OUTPUT_ENB") (class "Default")
      (node (ref "CN1") (pin "12") (pinfunction "12_12") (pintype "passive"))
    )
    (net (code "13") (name "/SPI_MOSI_1") (class "Default")
      (node (ref "U2") (pin "8") (pinfunction "D1/SDIN_8") (pintype "passive"))
    )
    (net (code "14") (name "/SPI_NSS_1") (class "Default")
      (node (ref "U2") (pin "17") (pinfunction "/CS_17") (pintype "passive"))
    )
    (net (code "15") (name "/SPI_SCK_1") (class "Default")
      (node (ref "U2") (pin "7") (pinfunction "D0/SCK_7") (pintype "passive"))
    )
    (net (code "16") (name "/Spare1") (class "Default")
      (node (ref "CN1") (pin "2") (pinfunction "2_2") (pintype "passive"))
    )
    (net (code "17") (name "/Spare2") (class "Default")
      (node (ref "CN1") (pin "1") (pinfunction "1_1") (pintype "passive"))
    )
    (net (code "18") (name "/VIN_CHK") (class "Default")
      (node (ref "C32") (pin "1") (pinfunction "1_1") (pintype "passive"))
      (node (ref "R23") (pin "1") (pinfunction "1_1") (pintype "passive"))
      (node (ref "R37") (pin "2") (pinfunction "2_2") (pintype "passive"))
    )
    (net (code "19") (name "/V_ENC_A") (class "Default")
      (node (ref "C37") (pin "1") (pinfunction "1_1") (pintype "passive"))
      (node (ref "R41") (pin "2") (pinfunction "2_2") (pintype "passive"))
      (node (ref "U1") (pin "21") (pinfunction "GPA0_21") (pintype "passive"))
    )
    (net (code "20") (name "/V_ENC_B") (class "Default")
      (node (ref "C36") (pin "1") (pinfunction "1_1") (pintype "passive"))
      (node (ref "R43") (pin "2") (pinfunction "2_2") (pintype "passive"))
      (node (ref "U1") (pin "22") (pinfunction "GPA1_22") (pintype "passive"))
    )
    (net (code "21") (name "/V_ENC_SW") (class "Default")
      (node (ref "C40") (pin "1") (pinfunction "1_1") (pintype "passive"))
      (node (ref "R42") (pin "1") (pinfunction "1_1") (pintype "passive"))
      (node (ref "U1") (pin "23") (pinfunction "GPA2_23") (pintype "passive"))
    )
    (net (code "22") (name "/{slash}CAP_T_INT") (class "Default")
      (node (ref "U1") (pin "27") (pinfunction "GPA6_27") (pintype "passive"))
    )
    (net (code "23") (name "/{slash}INT") (class "Default")
      (node (ref "R8") (pin "1") (pinfunction "1_1") (pintype "passive"))
      (node (ref "U1") (pin "19") (pinfunction "INTB_19") (pintype "passive"))
      (node (ref "U1") (pin "20") (pinfunction "INTA_20") (pintype "passive"))
    )
    (net (code "24") (name "/{slash}RST_MCP23017") (class "Default")
      (node (ref "R11") (pin "1") (pinfunction "1_1") (pintype "passive"))
      (node (ref "U1") (pin "18") (pinfunction "/RST_18") (pintype "passive"))
    )
    (net (code "25") (name "/{slash}RST_OLED") (class "Default")
      (node (ref "R48") (pin "1") (pinfunction "1_1") (pintype "passive"))
      (node (ref "U2") (pin "16") (pinfunction "/RES_16") (pintype "passive"))
    )
    (net (code "26") (name "3V3") (class "Default")
      (node (ref "3V3") (pin "1") (pinfunction "1_1") (pintype "passive"))
      (node (ref "C1") (pin "1") (pinfunction "1_1") (pintype "passive"))
      (node (ref "C14") (pin "1") (pinfunction "1_1") (pintype "passive"))
      (node (ref "C15") (pin "1") (pinfunction "1_1") (pintype "passive"))
      (node (ref "C2") (pin "1") (pinfunction "1_1") (pintype "passive"))
      (node (ref "C3") (pin "1") (pinfunction "1_1") (pintype "passive"))
      (node (ref "C33") (pin "1") (pinfunction "1_1") (pintype "passive"))
      (node (ref "C4") (pin "1") (pinfunction "1_1") (pintype "passive"))
      (node (ref "R10") (pin "2") (pinfunction "2_2") (pintype "passive"))
      (node (ref "R11") (pin "2") (pinfunction "2_2") (pintype "passive"))
      (node (ref "R14") (pin "2") (pinfunction "2_2") (pintype "passive"))
      (node (ref "R15") (pin "2") (pinfunction "2_2") (pintype "passive"))
      (node (ref "R16") (pin "2") (pinfunction "2_2") (pintype "passive"))
      (node (ref "R21") (pin "2") (pinfunction "2_2") (pintype "passive"))
      (node (ref "R38") (pin "2") (pinfunction "2_2") (pintype "passive"))
      (node (ref "R48") (pin "2") (pinfunction "2_2") (pintype "passive"))
      (node (ref "R5") (pin "2") (pinfunction "2_2") (pintype "passive"))
      (node (ref "R6") (pin "2") (pinfunction "2_2") (pintype "passive"))
      (node (ref "R7") (pin "2") (pinfunction "2_2") (pintype "passive"))
      (node (ref "R8") (pin "2") (pinfunction "2_2") (pintype "passive"))
      (node (ref "R9") (pin "2") (pinfunction "2_2") (pintype "passive"))
      (node (ref "U1") (pin "9") (pinfunction "VDD_9") (pintype "passive"))
      (node (ref "U2") (pin "2") (pinfunction "VDD_2") (pintype "passive"))
      (node (ref "U4") (pin "2") (pinfunction "VOUT_2") (pintype "power_in"))
      (node (ref "U4") (pin "4") (pinfunction "TAB_4") (pintype "power_in"))
      (node (ref "U6") (pin "5") (pinfunction "SENSE_5") (pintype "passive"))
      (node (ref "U6") (pin "6") (pinfunction "VDD_6") (pintype "passive"))
    )
    (net (code "27") (name "GND") (class "Default")
      (node (ref "C1") (pin "2") (pinfunction "2_2") (pintype "passive"))
      (node (ref "C10") (pin "2") (pinfunction "2_2") (pintype "passive"))
      (node (ref "C11") (pin "2") (pinfunction "2_2") (pintype "passive"))
      (node (ref "C12") (pin "2") (pinfunction "2_2") (pintype "passive"))
      (node (ref "C13") (pin "2") (pinfunction "2_2") (pintype "passive"))
      (node (ref "C14") (pin "2") (pinfunction "2_2") (pintype "passive"))
      (node (ref "C15") (pin "2") (pinfunction "2_2") (pintype "passive"))
      (node (ref "C16") (pin "2") (pinfunction "2_2") (pintype "passive"))
      (node (ref "C2") (pin "2") (pinfunction "2_2") (pintype "passive"))
      (node (ref "C27") (pin "2") (pinfunction "2_2") (pintype "passive"))
      (node (ref "C3") (pin "2") (pinfunction "2_2") (pintype "passive"))
      (node (ref "C31") (pin "2") (pinfunction "2_2") (pintype "passive"))
      (node (ref "C32") (pin "2") (pinfunction "2_2") (pintype "passive"))
      (node (ref "C33") (pin "2") (pinfunction "2_2") (pintype "passive"))
      (node (ref "C34") (pin "2") (pinfunction "2_2") (pintype "passive"))
      (node (ref "C36") (pin "2") (pinfunction "2_2") (pintype "passive"))
      (node (ref "C37") (pin "2") (pinfunction "2_2") (pintype "passive"))
      (node (ref "C39") (pin "2") (pinfunction "2_2") (pintype "passive"))
      (node (ref "C4") (pin "2") (pinfunction "2_2") (pintype "passive"))
      (node (ref "C40") (pin "2") (pinfunction "2_2") (pintype "passive"))
      (node (ref "C41") (pin "2") (pinfunction "2_2") (pintype "passive"))
      (node (ref "C7") (pin "2") (pinfunction "2_2") (pintype "passive"))
      (node (ref "C8") (pin "2") (pinfunction "2_2") (pintype "passive"))
      (node (ref "C9") (pin "2") (pinfunction "2_2") (pintype "passive"))
      (node (ref "CN1") (pin "15") (pinfunction "15_15") (pintype "passive"))
      (node (ref "CN1") (pin "16") (pinfunction "16_16") (pintype "passive"))
      (node (ref "CN1") (pin "7") (pinfunction "7_7") (pintype "passive"))
      (node (ref "CN1") (pin "8") (pinfunction "8_8") (pintype "passive"))
      (node (ref "CS1") (pin "2") (pinfunction "GND_2") (pintype "passive"))
      (node (ref "GND1") (pin "1") (pinfunction "1_1") (pintype "passive"))
      (node (ref "GND2") (pin "1") (pinfunction "1_1") (pintype "passive"))
      (node (ref "GND3") (pin "1") (pinfunction "1_1") (pintype "passive"))
      (node (ref "LED1") (pin "2") (pinfunction "2_2") (pintype "passive"))
      (node (ref "P1") (pin "1") (pinfunction "1_1") (pintype "passive"))
      (node (ref "Q1") (pin "1") (pinfunction "G_1") (pintype "passive"))
      (node (ref "Q3") (pin "2") (pinfunction "E_2") (pintype "passive"))
      (node (ref "R12") (pin "2") (pinfunction "2_2") (pintype "passive"))
      (node (ref "R18") (pin "1") (pinfunction "1_1") (pintype "passive"))
      (node (ref "R37") (pin "1") (pinfunction "1_1") (pintype "passive"))
      (node (ref "R46") (pin "1") (pinfunction "1_1") (pintype "passive"))
      (node (ref "R49") (pin "1") (pinfunction "1_1") (pintype "passive"))
      (node (ref "S1") (pin "2") (pinfunction "C_2") (pintype "passive"))
      (node (ref "S1") (pin "4") (pinfunction "F1_4") (pintype "passive"))
      (node (ref "S1") (pin "5") (pinfunction "S1_5") (pintype "passive"))
      (node (ref "S1") (pin "7") (pinfunction "F2_7") (pintype "passive"))
      (node (ref "S5") (pin "2") (pinfunction "C_2") (pintype "passive"))
      (node (ref "S5") (pin "4") (pinfunction "F1_4") (pintype "passive"))
      (node (ref "S5") (pin "5") (pinfunction "S1_5") (pintype "passive"))
      (node (ref "S5") (pin "7") (pinfunction "F2_7") (pintype "passive"))
      (node (ref "U1") (pin "10") (pinfunction "VSS_10") (pintype "passive"))
      (node (ref "U1") (pin "15") (pinfunction "A0_15") (pintype "passive"))
      (node (ref "U1") (pin "16") (pinfunction "A1_16") (pintype "passive"))
      (node (ref "U1") (pin "17") (pinfunction "A2_17") (pintype "passive"))
      (node (ref "U2") (pin "1") (pinfunction "VSS_1") (pintype "passive"))
      (node (ref "U2") (pin "10") (pinfunction "D3_10") (pintype "passive"))
      (node (ref "U2") (pin "11") (pinfunction "D4_11") (pintype "passive"))
      (node (ref "U2") (pin "12") (pinfunction "D5_12") (pintype "passive"))
      (node (ref "U2") (pin "13") (pinfunction "D6_13") (pintype "passive"))
      (node (ref "U2") (pin "14") (pinfunction "D7_14") (pintype "passive"))
      (node (ref "U2") (pin "19") (pinfunction "BS1_19") (pintype "passive"))
      (node (ref "U2") (pin "20") (pinfunction "BS0_20") (pintype "passive"))
      (node (ref "U2") (pin "5") (pinfunction "R/W_5") (pintype "passive"))
      (node (ref "U2") (pin "6") (pinfunction "E_6") (pintype "passive"))
      (node (ref "U3") (pin "1") (pinfunction "GND_1") (pintype "power_in"))
      (node (ref "U4") (pin "1") (pinfunction "GND_1") (pintype "power_in"))
      (node (ref "U6") (pin "2") (pinfunction "GND_2") (pintype "passive"))
      (node (ref "U7") (pin "2") (pinfunction "VSS_2") (pintype "passive"))
      (node (ref "U7") (pin "6") (pinfunction "TIME_6") (pintype "passive"))
    )
    (net (code "28") (name "Net-(CS1-SENSE)") (class "Default")
      (node (ref "CS1") (pin "1") (pinfunction "SENSE_1") (pintype "passive"))
      (node (ref "R50") (pin "1") (pinfunction "1_1") (pintype "passive"))
    )
    (net (code "29") (name "Net-(F1-Pad1)") (class "Default")
      (node (ref "F1") (pin "1") (pinfunction "1_1") (pintype "passive"))
      (node (ref "P1") (pin "2") (pinfunction "2_2") (pintype "passive"))
      (node (ref "R46") (pin "2") (pinfunction "2_2") (pintype "passive"))
    )
    (net (code "30") (name "Net-(J1-Jack)") (class "Default")
      (node (ref "C5") (pin "2") (pinfunction "2_2") (pintype "passive"))
      (node (ref "C6") (pin "2") (pinfunction "2_2") (pintype "passive"))
      (node (ref "CN4") (pin "10") (pinfunction "10_10") (pintype "passive"))
      (node (ref "CN4") (pin "4") (pinfunction "4_4") (pintype "passive"))
      (node (ref "CN4") (pin "5") (pinfunction "5_5") (pintype "passive"))
      (node (ref "CN4") (pin "9") (pinfunction "9_9") (pintype "passive"))
      (node (ref "J1") (pin "1") (pinfunction "Jack_1") (pintype "passive"))
      (node (ref "R17") (pin "1") (pinfunction "1_1") (pintype "passive"))
    )
    (net (code "31") (name "Net-(J2-Jack)") (class "Default")
      (node (ref "C5") (pin "1") (pinfunction "1_1") (pintype "passive"))
      (node (ref "C6") (pin "1") (pinfunction "1_1") (pintype "passive"))
      (node (ref "CN4") (pin "1") (pinfunction "1_1") (pintype "passive"))
      (node (ref "CN4") (pin "2") (pinfunction "2_2") (pintype "passive"))
      (node (ref "CN4") (pin "3") (pinfunction "3_3") (pintype "passive"))
      (node (ref "CN4") (pin "6") (pinfunction "6_6") (pintype "passive"))
      (node (ref "CN4") (pin "7") (pinfunction "7_7") (pintype "passive"))
      (node (ref "CN4") (pin "8") (pinfunction "8_8") (pintype "passive"))
      (node (ref "J2") (pin "1") (pinfunction "Jack_1") (pintype "passive"))
      (node (ref "R17") (pin "2") (pinfunction "2_2") (pintype "passive"))
    )
    (net (code "32") (name "Net-(LED1-Pad1)") (class "Default")
      (node (ref "LED1") (pin "1") (pinfunction "1_1") (pintype "passive"))
      (node (ref "R21") (pin "1") (pinfunction "1_1") (pintype "passive"))
    )
    (net (code "33") (name "Net-(Q1-D)") (class "Default")
      (node (ref "F1") (pin "2") (pinfunction "2_2") (pintype "passive"))
      (node (ref "Q1") (pin "3") (pinfunction "D_3") (pintype "passive"))
    )
    (net (code "34") (name "Net-(Q1-S)") (class "Default")
      (node (ref "C11") (pin "1") (pinfunction "1_1") (pintype "passive"))
      (node (ref "C7") (pin "1") (pinfunction "1_1") (pintype "passive"))
      (node (ref "FB1") (pin "1") (pinfunction "1_1") (pintype "passive"))
      (node (ref "Q1") (pin "2") (pinfunction "S_2") (pintype "passive"))
    )
    (net (code "35") (name "Net-(Q2-G)") (class "Default")
      (node (ref "Q2") (pin "1") (pinfunction "G_1") (pintype "passive"))
      (node (ref "Q3") (pin "3") (pinfunction "C_3") (pintype "passive"))
      (node (ref "R1") (pin "1") (pinfunction "1_1") (pintype "passive"))
    )
    (net (code "36") (name "Net-(Q3-B)") (class "Default")
      (node (ref "Q3") (pin "1") (pinfunction "B_1") (pintype "passive"))
      (node (ref "R12") (pin "1") (pinfunction "1_1") (pintype "passive"))
      (node (ref "R2") (pin "1") (pinfunction "1_1") (pintype "passive"))
    )
    (net (code "37") (name "Net-(S1-A)") (class "Default")
      (node (ref "R41") (pin "1") (pinfunction "1_1") (pintype "passive"))
      (node (ref "R7") (pin "1") (pinfunction "1_1") (pintype "passive"))
      (node (ref "S1") (pin "1") (pinfunction "A_1") (pintype "passive"))
    )
    (net (code "38") (name "Net-(S1-B)") (class "Default")
      (node (ref "R43") (pin "1") (pinfunction "1_1") (pintype "passive"))
      (node (ref "R5") (pin "1") (pinfunction "1_1") (pintype "passive"))
      (node (ref "S1") (pin "3") (pinfunction "B_3") (pintype "passive"))
    )
    (net (code "39") (name "Net-(S1-S2)") (class "Default")
      (node (ref "R42") (pin "2") (pinfunction "2_2") (pintype "passive"))
      (node (ref "R6") (pin "1") (pinfunction "1_1") (pintype "passive"))
      (node (ref "S1") (pin "6") (pinfunction "S2_6") (pintype "passive"))
    )
    (net (code "40") (name "Net-(S5-A)") (class "Default")
      (node (ref "R16") (pin "1") (pinfunction "1_1") (pintype "passive"))
      (node (ref "R27") (pin "1") (pinfunction "1_1") (pintype "passive"))
      (node (ref "S5") (pin "1") (pinfunction "A_1") (pintype "passive"))
    )
    (net (code "41") (name "Net-(S5-B)") (class "Default")
      (node (ref "R14") (pin "1") (pinfunction "1_1") (pintype "passive"))
      (node (ref "R28") (pin "1") (pinfunction "1_1") (pintype "passive"))
      (node (ref "S5") (pin "3") (pinfunction "B_3") (pintype "passive"))
    )
    (net (code "42") (name "Net-(S5-S2)") (class "Default")
      (node (ref "R15") (pin "1") (pinfunction "1_1") (pintype "passive"))
      (node (ref "R45") (pin "2") (pinfunction "2_2") (pintype "passive"))
      (node (ref "S5") (pin "6") (pinfunction "S2_6") (pintype "passive"))
    )
    (net (code "43") (name "Net-(U3-TAB)") (class "Default")
      (node (ref "C16") (pin "1") (pinfunction "1_1") (pintype "passive"))
      (node (ref "C41") (pin "1") (pinfunction "1_1") (pintype "passive"))
      (node (ref "R18") (pin "2") (pinfunction "2_2") (pintype "passive"))
      (node (ref "U3") (pin "2") (pinfunction "VOUT_2") (pintype "power_in"))
      (node (ref "U3") (pin "4") (pinfunction "TAB_4") (pintype "power_in"))
      (node (ref "U7") (pin "5") (pinfunction "VDD_5") (pintype "passive"))
    )
    (net (code "44") (name "Net-(U6-CT)") (class "Default")
      (node (ref "R38") (pin "1") (pinfunction "1_1") (pintype "passive"))
      (node (ref "U6") (pin "4") (pinfunction "CT_4") (pintype "passive"))
    )
    (net (code "45") (name "Net-(U6-{slash}MR)") (class "Default")
      (node (ref "/MR") (pin "1") (pinfunction "1_1") (pintype "passive"))
      (node (ref "U6") (pin "3") (pinfunction "/MR_3") (pintype "passive"))
    )
    (net (code "46") (name "Net-(U7-OUT)") (class "Default")
      (node (ref "R2") (pin "2") (pinfunction "2_2") (pintype "passive"))
      (node (ref "U7") (pin "1") (pinfunction "OUT_1") (pintype "passive"))
    )
    (net (code "47") (name "Net-(U7-SNS)") (class "Default")
      (node (ref "C42") (pin "1") (pinfunction "1_1") (pintype "passive"))
      (node (ref "R49") (pin "2") (pinfunction "2_2") (pintype "passive"))
      (node (ref "U7") (pin "4") (pinfunction "SNS_4") (pintype "passive"))
    )
    (net (code "48") (name "Net-(U7-SNSK)") (class "Default")
      (node (ref "C42") (pin "2") (pinfunction "2_2") (pintype "passive"))
      (node (ref "R50") (pin "2") (pinfunction "2_2") (pintype "passive"))
      (node (ref "U7") (pin "3") (pinfunction "SNSK_3") (pintype "passive"))
    )
    (net (code "49") (name "unconnected-(CN1-Pad4)") (class "Default")
      (node (ref "CN1") (pin "4") (pinfunction "4_4") (pintype "passive+no_connect"))
    )
    (net (code "50") (name "unconnected-(U1-GPA7-Pad28)") (class "Default")
      (node (ref "U1") (pin "28") (pinfunction "GPA7_28") (pintype "passive+no_connect"))
    )
    (net (code "51") (name "unconnected-(U1-GPB0-Pad1)") (class "Default")
      (node (ref "U1") (pin "1") (pinfunction "GPB0_1") (pintype "passive+no_connect"))
    )
    (net (code "52") (name "unconnected-(U1-GPB1-Pad2)") (class "Default")
      (node (ref "U1") (pin "2") (pinfunction "GPB1_2") (pintype "passive+no_connect"))
    )
    (net (code "53") (name "unconnected-(U1-GPB2-Pad3)") (class "Default")
      (node (ref "U1") (pin "3") (pinfunction "GPB2_3") (pintype "passive"))
    )
    (net (code "54") (name "unconnected-(U1-GPB3-Pad4)") (class "Default")
      (node (ref "U1") (pin "4") (pinfunction "GPB3_4") (pintype "passive"))
    )
    (net (code "55") (name "unconnected-(U1-GPB4-Pad5)") (class "Default")
      (node (ref "U1") (pin "5") (pinfunction "GPB4_5") (pintype "passive+no_connect"))
    )
    (net (code "56") (name "unconnected-(U1-GPB5-Pad6)") (class "Default")
      (node (ref "U1") (pin "6") (pinfunction "GPB5_6") (pintype "passive"))
    )
    (net (code "57") (name "unconnected-(U1-GPB6-Pad7)") (class "Default")
      (node (ref "U1") (pin "7") (pinfunction "GPB6_7") (pintype "passive+no_connect"))
    )
    (net (code "58") (name "unconnected-(U1-GPB7-Pad8)") (class "Default")
      (node (ref "U1") (pin "8") (pinfunction "GPB7_8") (pintype "passive+no_connect"))
    )
    (net (code "59") (name "unconnected-(U1-NC-Pad11)") (class "Default")
      (node (ref "U1") (pin "11") (pinfunction "NC_11") (pintype "passive+no_connect"))
    )
    (net (code "60") (name "unconnected-(U1-NC-Pad14)") (class "Default")
      (node (ref "U1") (pin "14") (pinfunction "NC_14") (pintype "passive+no_connect"))
    )
    (net (code "61") (name "unconnected-(U2-D2-Pad9)") (class "Default")
      (node (ref "U2") (pin "9") (pinfunction "D2_9") (pintype "passive+no_connect"))
    )
    (net (code "62") (name "unconnected-(U2-NC-Pad3)") (class "Default")
      (node (ref "U2") (pin "3") (pinfunction "NC_3") (pintype "passive+no_connect"))
    )
    (net (code "63") (name "unconnected-(U2-NC-Pad15)") (class "Default")
      (node (ref "U2") (pin "15") (pinfunction "NC_15") (pintype "passive+no_connect"))
    )
    (net (code "64") (name "unconnected-(U2-NC-Pad18)") (class "Default")
      (node (ref "U2") (pin "18") (pinfunction "NC_18") (pintype "passive+no_connect"))
    )
  )
)
